# Sek_CTRL.net
KiCad netlist of a schematic drawn in Altium Designer
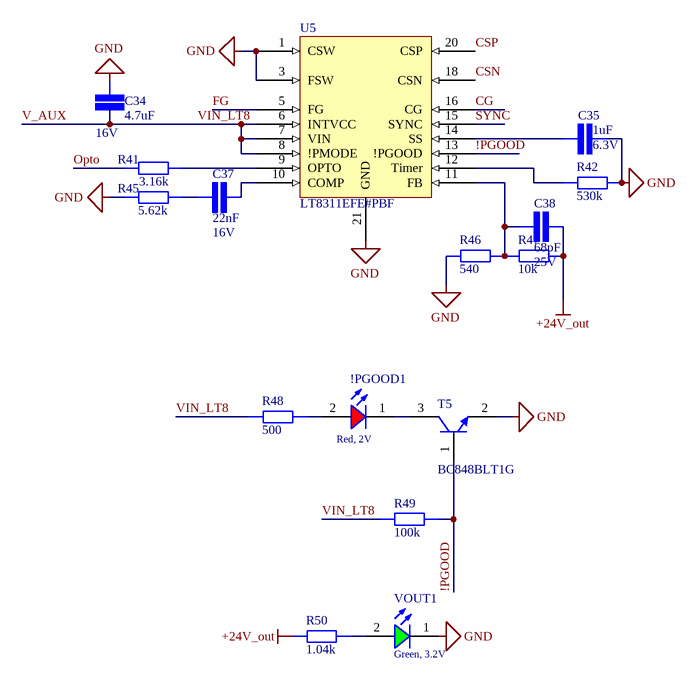
[diagram p0: Sek_CTRL.SchDoc]

(export (version "E")
  (design (tool "Eeschema 10.0.6"))
  (components
    (comp (ref "!PGOOD1")
      (value "Red, 2V")
      (footprint "WL-SMCW_0603_H=0.7mm")
      (description "WL-SMCW SMT Mono-color Chip LED Waterclear, size 0603, Red, 2V, 140deg")
      (fields (field (name "PART NUMBER") "150060RS75000") (field (name "PUBLISHER") "Wurth Elektronik"))
      (libsource (lib "Altium_WL-SMCW (rev20a)") (part "150060RS75000"))
    )
    (comp (ref "C34")
      (value "4.7uF")
      (footprint "CAP 0603/1608")
      (description "Capacitor with multiple Footprints")
      (fields (field (name "VOLTAGE") "16V") (field (name "Comment") "SMD Capacitor"))
      (libsource (lib "") (part "SMD Capacitor_1"))
    )
    (comp (ref "C35")
      (value "1uF")
      (footprint "CAP 0603/1608")
      (description "Capacitor with multiple Footprints")
      (fields (field (name "VOLTAGE") "6.3V") (field (name "Comment") "SMD Capacitor"))
      (libsource (lib "Standardbauteile") (part "SMD Capacitor"))
    )
    (comp (ref "C37")
      (value "22nF")
      (footprint "CAP 0603/1608")
      (description "Capacitor with multiple Footprints")
      (fields (field (name "VOLTAGE") "16V") (field (name "Comment") "SMD Capacitor"))
      (libsource (lib "Standardbauteile") (part "SMD Capacitor"))
    )
    (comp (ref "C38")
      (value "68pF")
      (footprint "CAP 0603/1608")
      (description "Capacitor with multiple Footprints")
      (fields (field (name "VOLTAGE") "25V") (field (name "Comment") "SMD Capacitor"))
      (libsource (lib "Standardbauteile") (part "SMD Capacitor"))
    )
    (comp (ref "R41")
      (value "3.16k")
      (footprint "STACKPOLE CSR0603")
      (description "Resistor with multiple footprints")
      (fields (field (name "Comment") "SMD Resistor"))
      (libsource (lib "Standardbauteile") (part "SMD Resistor"))
    )
    (comp (ref "R42")
      (value "530k")
      (footprint "STACKPOLE CSR0603")
      (description "Resistor with multiple footprints")
      (fields (field (name "Comment") "SMD Resistor"))
      (libsource (lib "Standardbauteile") (part "SMD Resistor"))
    )
    (comp (ref "R45")
      (value "5.62k")
      (footprint "STACKPOLE CSR0603")
      (description "Resistor with multiple footprints")
      (fields (field (name "Comment") "SMD Resistor"))
      (libsource (lib "Standardbauteile") (part "SMD Resistor"))
    )
    (comp (ref "R46")
      (value "540")
      (footprint "STACKPOLE CSR0603")
      (description "Resistor with multiple footprints")
      (fields (field (name "Comment") "SMD Resistor"))
      (libsource (lib "Standardbauteile") (part "SMD Resistor"))
    )
    (comp (ref "R47")
      (value "10k")
      (footprint "STACKPOLE CSR0603")
      (description "Resistor with multiple footprints")
      (fields (field (name "Comment") "SMD Resistor"))
      (libsource (lib "Standardbauteile") (part "SMD Resistor"))
    )
    (comp (ref "R48")
      (value "500")
      (footprint "STACKPOLE CSR0603")
      (description "Resistor with multiple footprints")
      (fields (field (name "Comment") "SMD Resistor"))
      (libsource (lib "Standardbauteile") (part "SMD Resistor"))
    )
    (comp (ref "R49")
      (value "100k")
      (footprint "STACKPOLE CSR0603")
      (description "Resistor with multiple footprints")
      (fields (field (name "Comment") "SMD Resistor"))
      (libsource (lib "Standardbauteile") (part "SMD Resistor"))
    )
    (comp (ref "R50")
      (value "1.04k")
      (footprint "STACKPOLE CSR0603")
      (description "Resistor with multiple footprints")
      (fields (field (name "Comment") "SMD Resistor"))
      (libsource (lib "Standardbauteile") (part "SMD Resistor"))
    )
    (comp (ref "T5")
      (value "BC848BLT1G")
      (footprint "ONSC-SOT-23-3-318-08_V")
      (description "General Purpose Transistor, NPN Silicon, 3-Pin SOT-23, Pb-Free, Tape and Reel")
      (fields (field (name "MANUFACTURER") "On Semiconductor"))
      (libsource (lib "Altium Content Vault") (part "ONSC-NPN-B1E2C3-3"))
    )
    (comp (ref "U5")
      (value "LT8311EFE#PBF")
      (footprint "TSSOP 20 Lead LT8311")
      (description "LT8311 - Synchronous Rectifier Controller with Opto-Coupler Driver for Forward Converters")
      (fields (field (name "MANUFACTURER") "Analog Devices / Linear Technology"))
      (libsource (lib "Integrated_LibraryLukas_New") (part "LT8311EFE#PBF"))
    )
    (comp (ref "VOUT1")
      (value "Green, 3.2V")
      (footprint "WL-SMCW_0603_H=0.7mm")
      (description "WL-SMCW SMT Mono-color Chip LED Waterclear, size 0603, Green, 3.2V, 140deg")
      (fields (field (name "PART NUMBER") "150060GS75000") (field (name "PUBLISHER") "Wurth Elektronik"))
      (libsource (lib "Altium_WL-SMCW (rev20a)") (part "150060GS75000"))
    )
  )
  (nets
    (net (code "1") (name "+24V_out") (class "Default")
      (node (ref "C38") (pin "2") (pinfunction "2_2") (pintype "passive"))
      (node (ref "R47") (pin "1") (pinfunction "1_1") (pintype "passive"))
      (node (ref "R50") (pin "1") (pinfunction "1_1") (pintype "passive"))
    )
    (net (code "2") (name "/!PGOOD") (class "Default")
      (node (ref "R49") (pin "1") (pinfunction "1_1") (pintype "passive"))
      (node (ref "T5") (pin "1") (pinfunction "B_1") (pintype "passive"))
      (node (ref "U5") (pin "13") (pinfunction "!PGOOD_13") (pintype "input"))
    )
    (net (code "3") (name "/CG") (class "Default")
      (node (ref "U5") (pin "16") (pinfunction "CG_16") (pintype "input"))
    )
    (net (code "4") (name "/CSN") (class "Default")
      (node (ref "U5") (pin "18") (pinfunction "CSN_18") (pintype "input"))
    )
    (net (code "5") (name "/CSP") (class "Default")
      (node (ref "U5") (pin "20") (pinfunction "CSP_20") (pintype "input"))
    )
    (net (code "6") (name "/FG") (class "Default")
      (node (ref "U5") (pin "5") (pinfunction "FG_5") (pintype "input"))
    )
    (net (code "7") (name "/Opto") (class "Default")
      (node (ref "R41") (pin "1") (pinfunction "1_1") (pintype "passive"))
    )
    (net (code "8") (name "/SYNC") (class "Default")
      (node (ref "U5") (pin "15") (pinfunction "SYNC_15") (pintype "input"))
    )
    (net (code "9") (name "/VIN_LT8") (class "Default")
      (node (ref "C34") (pin "1") (pinfunction "1_1") (pintype "passive"))
      (node (ref "R48") (pin "2") (pinfunction "2_2") (pintype "passive"))
      (node (ref "R49") (pin "2") (pinfunction "2_2") (pintype "passive"))
      (node (ref "U5") (pin "6") (pinfunction "INTVCC_6") (pintype "input"))
      (node (ref "U5") (pin "7") (pinfunction "VIN_7") (pintype "input"))
      (node (ref "U5") (pin "8") (pinfunction "!PMODE_8") (pintype "input"))
    )
    (net (code "10") (name "GND") (class "Default")
      (node (ref "C34") (pin "2") (pinfunction "2_2") (pintype "passive"))
      (node (ref "C35") (pin "2") (pinfunction "2_2") (pintype "passive"))
      (node (ref "R42") (pin "2") (pinfunction "2_2") (pintype "passive"))
      (node (ref "R45") (pin "2") (pinfunction "2_2") (pintype "passive"))
      (node (ref "R46") (pin "2") (pinfunction "2_2") (pintype "passive"))
      (node (ref "T5") (pin "2") (pinfunction "E_2") (pintype "passive"))
      (node (ref "U5") (pin "1") (pinfunction "CSW_1") (pintype "input"))
      (node (ref "U5") (pin "21") (pinfunction "GND_21") (pintype "passive"))
      (node (ref "U5") (pin "3") (pinfunction "FSW_3") (pintype "input"))
      (node (ref "VOUT1") (pin "1") (pinfunction "K_1") (pintype "passive"))
    )
    (net (code "11") (name "Net-(!PGOOD1-A)") (class "Default")
      (node (ref "!PGOOD1") (pin "2") (pinfunction "A_2") (pintype "passive"))
      (node (ref "R48") (pin "1") (pinfunction "1_1") (pintype "passive"))
    )
    (net (code "12") (name "Net-(!PGOOD1-K)") (class "Default")
      (node (ref "!PGOOD1") (pin "1") (pinfunction "K_1") (pintype "passive"))
      (node (ref "T5") (pin "3") (pinfunction "C_3") (pintype "passive"))
    )
    (net (code "13") (name "Net-(C37-Pad1)") (class "Default")
      (node (ref "C37") (pin "1") (pinfunction "1_1") (pintype "passive"))
      (node (ref "R45") (pin "1") (pinfunction "1_1") (pintype "passive"))
    )
    (net (code "14") (name "Net-(U5-COMP)") (class "Default")
      (node (ref "C37") (pin "2") (pinfunction "2_2") (pintype "passive"))
      (node (ref "U5") (pin "10") (pinfunction "COMP_10") (pintype "input"))
    )
    (net (code "15") (name "Net-(U5-FB)") (class "Default")
      (node (ref "C38") (pin "1") (pinfunction "1_1") (pintype "passive"))
      (node (ref "R46") (pin "1") (pinfunction "1_1") (pintype "passive"))
      (node (ref "R47") (pin "2") (pinfunction "2_2") (pintype "passive"))
      (node (ref "U5") (pin "11") (pinfunction "FB_11") (pintype "input"))
    )
    (net (code "16") (name "Net-(U5-OPTO)") (class "Default")
      (node (ref "R41") (pin "2") (pinfunction "2_2") (pintype "passive"))
      (node (ref "U5") (pin "9") (pinfunction "OPTO_9") (pintype "input"))
    )
    (net (code "17") (name "Net-(U5-SS)") (class "Default")
      (node (ref "C35") (pin "1") (pinfunction "1_1") (pintype "passive"))
      (node (ref "U5") (pin "14") (pinfunction "SS_14") (pintype "input"))
    )
    (net (code "18") (name "Net-(U5-Timer)") (class "Default")
      (node (ref "R42") (pin "1") (pinfunction "1_1") (pintype "passive"))
      (node (ref "U5") (pin "12") (pinfunction "Timer_12") (pintype "input"))
    )
    (net (code "19") (name "Net-(VOUT1-A)") (class "Default")
      (node (ref "R50") (pin "2") (pinfunction "2_2") (pintype "passive"))
      (node (ref "VOUT1") (pin "2") (pinfunction "A_2") (pintype "passive"))
    )
  )
)
